# Analog_power.net
KiCad netlist of a schematic drawn in Altium Designer
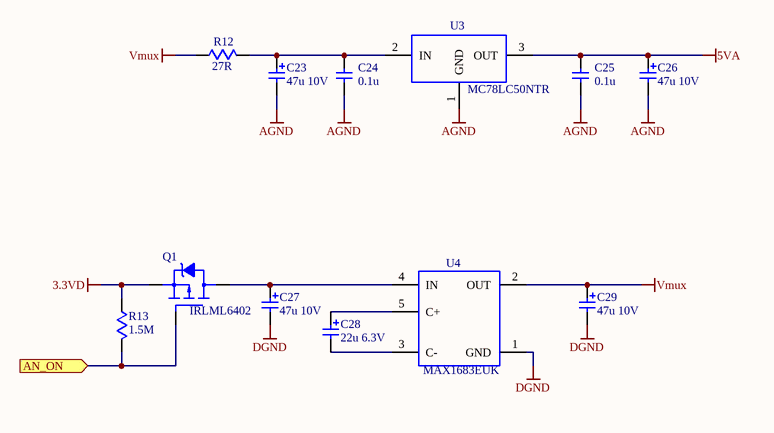
[diagram p0: Analog power.SchDoc]

(export (version "E")
  (design (tool "Eeschema 10.0.6"))
  (components
    (comp (ref "C23")
      (value "47u 10V")
      (footprint "SMD/C/TAJ-B")
      (libsource (lib "My_lib") (part "Capacitor Pol"))
    )
    (comp (ref "C24") (value "0.1u") (footprint "SMD/C/0603") (libsource (lib "My_lib") (part "Capacitor")))
    (comp (ref "C25") (value "0.1u") (footprint "SMD/C/0603") (libsource (lib "My_lib") (part "Capacitor")))
    (comp (ref "C26")
      (value "47u 10V")
      (footprint "SMD/C/TAJ-B")
      (libsource (lib "My_lib") (part "Capacitor Pol"))
    )
    (comp (ref "C27")
      (value "47u 10V")
      (footprint "SMD/C/TAJ-B")
      (libsource (lib "My_lib") (part "Capacitor Pol"))
    )
    (comp (ref "C28")
      (value "22u 6.3V")
      (footprint "SMD/C/TAJ-A")
      (libsource (lib "") (part "Capacitor Pol_1"))
    )
    (comp (ref "C29")
      (value "47u 10V")
      (footprint "SMD/C/TAJ-B")
      (libsource (lib "My_lib") (part "Capacitor Pol"))
    )
    (comp (ref "Q1")
      (value "IRLML6402")
      (footprint "SMD/SOT23")
      (description "P-channel HEXFET Power MOSFET")
      (libsource (lib "My_lib") (part "IRLML6402"))
    )
    (comp (ref "R12") (value "27R") (footprint "SMD/R/0603") (libsource (lib "My_lib") (part "Resistor")))
    (comp (ref "R13") (value "1.5M") (footprint "SMD/R/0603") (libsource (lib "My_lib") (part "Resistor")))
    (comp (ref "U3")
      (value "MC78LC50NTR")
      (footprint "SMD/SOT23-5")
      (description "Micropower Ultra-Low Quiescent Current Voltage Regulator")
      (libsource (lib "My_lib") (part "MC78LC50NTR"))
    )
    (comp (ref "U4")
      (value "MAX1683EUK")
      (footprint "SMD/SOT23-5")
      (description "Switched-Capacitor Voltage Doubler")
      (libsource (lib "My_lib") (part "MAX1683EUK"))
    )
  )
  (nets
    (net (code "1") (name "/AN_ON") (class "Default")
      (node (ref "Q1") (pin "1") (pinfunction "G_1") (pintype "passive"))
      (node (ref "R13") (pin "2") (pinfunction "2_2") (pintype "passive"))
    )
    (net (code "2") (name "3.3VD") (class "Default")
      (node (ref "Q1") (pin "2") (pinfunction "S_2") (pintype "passive"))
      (node (ref "R13") (pin "1") (pinfunction "1_1") (pintype "passive"))
    )
    (net (code "3") (name "5VA") (class "Default")
      (node (ref "C25") (pin "2") (pinfunction "2_2") (pintype "passive"))
      (node (ref "C26") (pin "P") (pinfunction "P_P") (pintype "passive"))
      (node (ref "U3") (pin "3") (pinfunction "OUT_3") (pintype "power_in"))
    )
    (net (code "4") (name "AGND") (class "Default")
      (node (ref "C23") (pin "M") (pinfunction "M_M") (pintype "passive"))
      (node (ref "C24") (pin "1") (pinfunction "1_1") (pintype "passive"))
      (node (ref "C25") (pin "1") (pinfunction "1_1") (pintype "passive"))
      (node (ref "C26") (pin "M") (pinfunction "M_M") (pintype "passive"))
      (node (ref "U3") (pin "1") (pinfunction "GND_1") (pintype "power_in"))
    )
    (net (code "5") (name "DGND") (class "Default")
      (node (ref "C27") (pin "M") (pinfunction "M_M") (pintype "passive"))
      (node (ref "C29") (pin "M") (pinfunction "M_M") (pintype "passive"))
      (node (ref "U4") (pin "1") (pinfunction "GND_1") (pintype "power_in"))
    )
    (net (code "6") (name "Net-(Q1-D)") (class "Default")
      (node (ref "C27") (pin "P") (pinfunction "P_P") (pintype "passive"))
      (node (ref "Q1") (pin "3") (pinfunction "D_3") (pintype "passive"))
      (node (ref "U4") (pin "4") (pinfunction "IN_4") (pintype "power_in"))
    )
    (net (code "7") (name "Net-(U3-IN)") (class "Default")
      (node (ref "C23") (pin "P") (pinfunction "P_P") (pintype "passive"))
      (node (ref "C24") (pin "2") (pinfunction "2_2") (pintype "passive"))
      (node (ref "R12") (pin "2") (pinfunction "2_2") (pintype "passive"))
      (node (ref "U3") (pin "2") (pinfunction "IN_2") (pintype "power_in"))
    )
    (net (code "8") (name "Net-(U4-C+)") (class "Default")
      (node (ref "C28") (pin "P") (pinfunction "P_P") (pintype "passive"))
      (node (ref "U4") (pin "5") (pinfunction "C+_5") (pintype "power_in"))
    )
    (net (code "9") (name "Net-(U4-C-)") (class "Default")
      (node (ref "C28") (pin "M") (pinfunction "M_M") (pintype "passive"))
      (node (ref "U4") (pin "3") (pinfunction "C-_3") (pintype "power_in"))
    )
    (net (code "10") (name "Vmux") (class "Default")
      (node (ref "C29") (pin "P") (pinfunction "P_P") (pintype "passive"))
      (node (ref "R12") (pin "1") (pinfunction "1_1") (pintype "passive"))
      (node (ref "U4") (pin "2") (pinfunction "OUT_2") (pintype "power_in"))
    )
  )
)
